# Attiny_Neopixel_Button.net
KiCad netlist of a schematic drawn in EAGLE
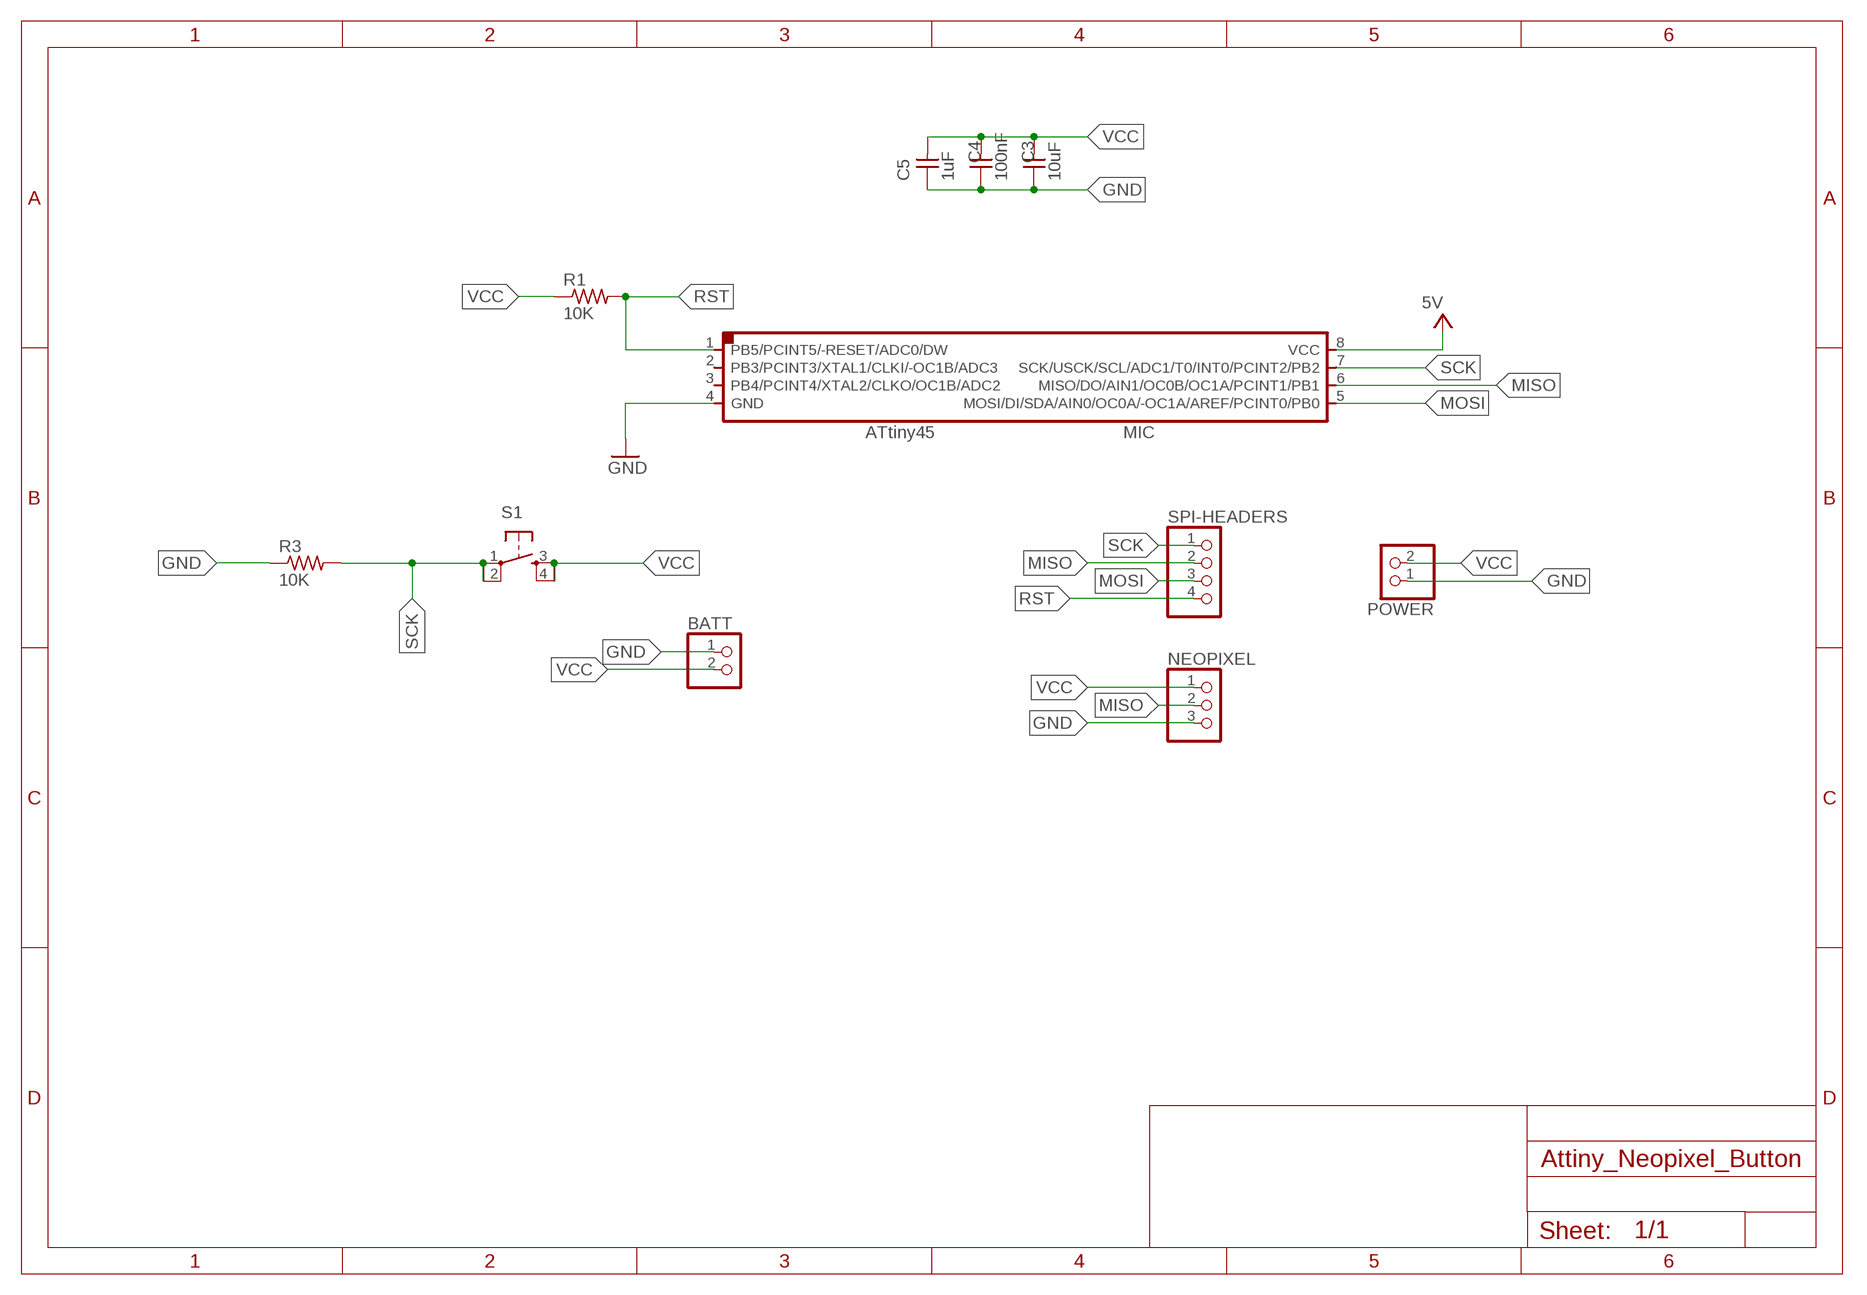
[diagram p0: schematic, sheet 1]

(export (version "E")
  (design (tool "Eeschema 10.0.6"))
  (components
    (comp (ref "BATT")
      (value "PINHD-1X2")
      (footprint "eagle-import:1X02")
      (libsource (lib "eagle-import") (part "PINHD-1X2"))
    )
    (comp (ref "C3")
      (value "10uF")
      (footprint "eagle-import:1206")
      (libsource (lib "eagle-import") (part "UNPOLARIZED_CAPACITOR1206"))
    )
    (comp (ref "C4")
      (value "100nF")
      (footprint "eagle-import:1206")
      (libsource (lib "eagle-import") (part "UNPOLARIZED_CAPACITOR1206"))
    )
    (comp (ref "C5")
      (value "1uF")
      (footprint "eagle-import:1206")
      (libsource (lib "eagle-import") (part "UNPOLARIZED_CAPACITOR1206"))
    )
    (comp (ref "MIC")
      (value "ATTINY45SI")
      (footprint "eagle-import:SOIC8")
      (libsource (lib "eagle-import") (part "ATTINY45SI"))
    )
    (comp (ref "NEOPIXEL")
      (value "PINHD-1X3")
      (footprint "eagle-import:1X03")
      (libsource (lib "eagle-import") (part "PINHD-1X3"))
    )
    (comp (ref "POWER")
      (value "PINHD-1X2")
      (footprint "eagle-import:1X02")
      (libsource (lib "eagle-import") (part "PINHD-1X2"))
    )
    (comp (ref "R1")
      (value "10K")
      (footprint "eagle-import:1206")
      (libsource (lib "eagle-import") (part "RESISTOR1206"))
    )
    (comp (ref "R3")
      (value "10K")
      (footprint "eagle-import:1206")
      (libsource (lib "eagle-import") (part "RESISTOR1206"))
    )
    (comp (ref "S1")
      (value "6MM_SWITCH6MM_SWITCH")
      (footprint "eagle-import:6MM_SWITCH")
      (libsource (lib "eagle-import") (part "6MM_SWITCH6MM_SWITCH"))
    )
    (comp (ref "SPI-HEADERS")
      (value "PINHD-1X4")
      (footprint "eagle-import:1X04")
      (libsource (lib "eagle-import") (part "PINHD-1X4"))
    )
  )
  (nets
    (net (code "1") (name "GND") (class "Default")
      (node (ref "BATT") (pin "1") (pinfunction "1_1") (pintype "passive"))
      (node (ref "C3") (pin "1") (pinfunction "1_1") (pintype "passive"))
      (node (ref "C4") (pin "1") (pinfunction "1_1") (pintype "passive"))
      (node (ref "C5") (pin "1") (pinfunction "1_1") (pintype "passive"))
      (node (ref "MIC") (pin "4") (pinfunction "GND_4") (pintype "bidirectional"))
      (node (ref "NEOPIXEL") (pin "3") (pinfunction "3_3") (pintype "passive"))
      (node (ref "POWER") (pin "1") (pinfunction "1_1") (pintype "passive"))
      (node (ref "R3") (pin "1") (pinfunction "1_1") (pintype "passive"))
    )
    (net (code "2") (name "MISO") (class "Default")
      (node (ref "MIC") (pin "6") (pinfunction "MISO/DO/AIN1/OC0B/OC1A/PCINT1/PB1_6") (pintype "bidirectional"))
      (node (ref "NEOPIXEL") (pin "2") (pinfunction "2_2") (pintype "passive"))
      (node (ref "SPI-HEADERS") (pin "2") (pinfunction "2_2") (pintype "passive"))
    )
    (net (code "3") (name "MOSI") (class "Default")
      (node (ref "MIC") (pin "5") (pinfunction "MOSI/DI/SDA/AIN0/OC0A/-OC1A/AREF/PCINT0/PB0_5") (pintype "bidirectional"))
      (node (ref "SPI-HEADERS") (pin "3") (pinfunction "3_3") (pintype "passive"))
    )
    (net (code "4") (name "RST") (class "Default")
      (node (ref "MIC") (pin "1") (pinfunction "PB5/PCINT5/-RESET/ADC0/DW_1") (pintype "bidirectional"))
      (node (ref "R1") (pin "2") (pinfunction "2_2") (pintype "passive"))
      (node (ref "SPI-HEADERS") (pin "4") (pinfunction "4_4") (pintype "passive"))
    )
    (net (code "5") (name "SCK") (class "Default")
      (node (ref "MIC") (pin "7") (pinfunction "SCK/USCK/SCL/ADC1/T0/INT0/PCINT2/PB2_7") (pintype "bidirectional"))
      (node (ref "R3") (pin "2") (pinfunction "2_2") (pintype "passive"))
      (node (ref "S1") (pin "1") (pinfunction "P_1") (pintype "passive"))
      (node (ref "S1") (pin "2") (pinfunction "P1_2") (pintype "passive"))
      (node (ref "SPI-HEADERS") (pin "1") (pinfunction "1_1") (pintype "passive"))
    )
    (net (code "6") (name "VCC") (class "Default")
      (node (ref "BATT") (pin "2") (pinfunction "2_2") (pintype "passive"))
      (node (ref "C3") (pin "2") (pinfunction "2_2") (pintype "passive"))
      (node (ref "C4") (pin "2") (pinfunction "2_2") (pintype "passive"))
      (node (ref "C5") (pin "2") (pinfunction "2_2") (pintype "passive"))
      (node (ref "MIC") (pin "8") (pinfunction "VCC_8") (pintype "bidirectional"))
      (node (ref "NEOPIXEL") (pin "1") (pinfunction "1_1") (pintype "passive"))
      (node (ref "POWER") (pin "2") (pinfunction "2_2") (pintype "passive"))
      (node (ref "R1") (pin "1") (pinfunction "1_1") (pintype "passive"))
      (node (ref "S1") (pin "3") (pinfunction "S_3") (pintype "passive"))
      (node (ref "S1") (pin "4") (pinfunction "S1_4") (pintype "passive"))
    )
    (net (code "7") (name "unconnected-(MIC-PB3{slash}PCINT3{slash}XTAL1{slash}CLKI{slash}-OC1B{slash}ADC3-Pad2)") (class "Default")
      (node (ref "MIC") (pin "2") (pinfunction "PB3/PCINT3/XTAL1/CLKI/-OC1B/ADC3_2") (pintype "bidirectional"))
    )
    (net (code "8") (name "unconnected-(MIC-PB4{slash}PCINT4{slash}XTAL2{slash}CLKO{slash}OC1B{slash}ADC2-Pad3)") (class "Default")
      (node (ref "MIC") (pin "3") (pinfunction "PB4/PCINT4/XTAL2/CLKO/OC1B/ADC2_3") (pintype "bidirectional"))
    )
  )
)
